# VRef_MEZ.net
KiCad netlist of a schematic drawn in Altium Designer
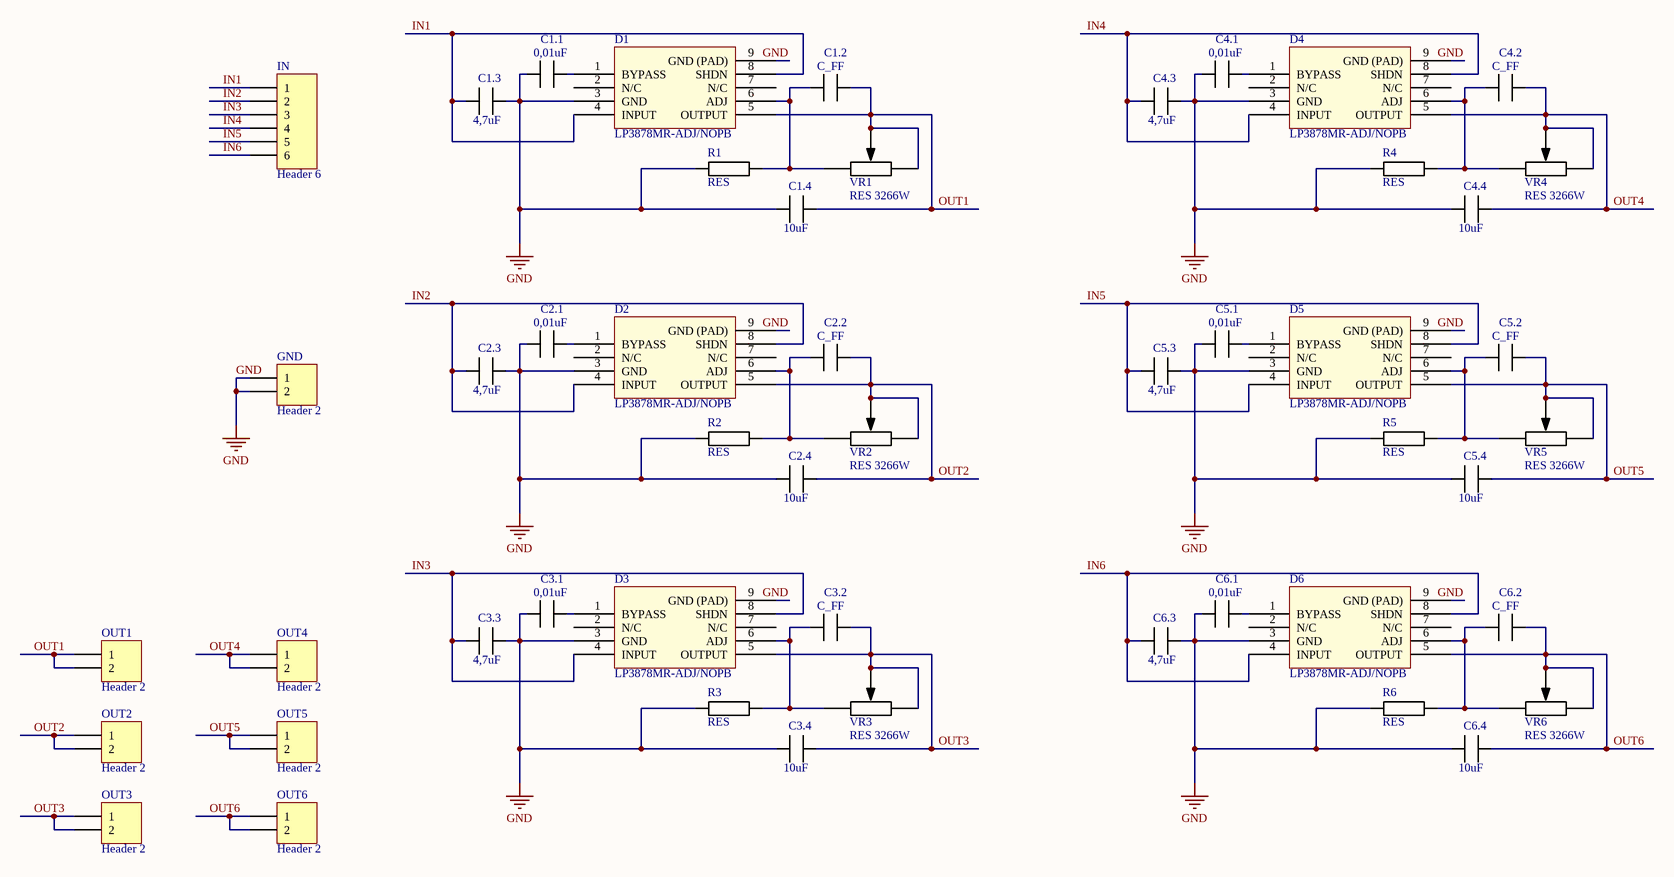
[diagram p0: VRef_MEZ.SchDoc]

(export (version "E")
  (design (tool "Eeschema 10.0.6"))
  (components
    (comp (ref "C1.1")
      (value "0,01uF")
      (footprint "aab_Passive:CAP_1812")
      (libsource (lib "aab_Schlib") (part "CAP"))
    )
    (comp (ref "C1.2")
      (value "C_FF")
      (footprint "aab_Passive:CAP_1812")
      (libsource (lib "aab_Schlib") (part "CAP"))
    )
    (comp (ref "C1.3")
      (value "4,7uF")
      (footprint "aab_Passive:CAP_1812")
      (libsource (lib "aab_Schlib") (part "CAP"))
    )
    (comp (ref "C1.4")
      (value "10uF")
      (footprint "aab_Passive:CAP_1812")
      (libsource (lib "aab_Schlib") (part "CAP"))
    )
    (comp (ref "C2.1")
      (value "0,01uF")
      (footprint "aab_Passive:CAP_1812")
      (libsource (lib "aab_Schlib") (part "CAP"))
    )
    (comp (ref "C2.2")
      (value "C_FF")
      (footprint "aab_Passive:CAP_1812")
      (libsource (lib "aab_Schlib") (part "CAP"))
    )
    (comp (ref "C2.3")
      (value "4,7uF")
      (footprint "aab_Passive:CAP_1812")
      (libsource (lib "aab_Schlib") (part "CAP"))
    )
    (comp (ref "C2.4")
      (value "10uF")
      (footprint "aab_Passive:CAP_1812")
      (libsource (lib "aab_Schlib") (part "CAP"))
    )
    (comp (ref "C3.1")
      (value "0,01uF")
      (footprint "aab_Passive:CAP_1812")
      (libsource (lib "aab_Schlib") (part "CAP"))
    )
    (comp (ref "C3.2")
      (value "C_FF")
      (footprint "aab_Passive:CAP_1812")
      (libsource (lib "aab_Schlib") (part "CAP"))
    )
    (comp (ref "C3.3")
      (value "4,7uF")
      (footprint "aab_Passive:CAP_1812")
      (libsource (lib "aab_Schlib") (part "CAP"))
    )
    (comp (ref "C3.4")
      (value "10uF")
      (footprint "aab_Passive:CAP_1812")
      (libsource (lib "aab_Schlib") (part "CAP"))
    )
    (comp (ref "C4.1")
      (value "0,01uF")
      (footprint "aab_Passive:CAP_1812")
      (libsource (lib "aab_Schlib") (part "CAP"))
    )
    (comp (ref "C4.2")
      (value "C_FF")
      (footprint "aab_Passive:CAP_1812")
      (libsource (lib "aab_Schlib") (part "CAP"))
    )
    (comp (ref "C4.3")
      (value "4,7uF")
      (footprint "aab_Passive:CAP_1812")
      (libsource (lib "aab_Schlib") (part "CAP"))
    )
    (comp (ref "C4.4")
      (value "10uF")
      (footprint "aab_Passive:CAP_1812")
      (libsource (lib "aab_Schlib") (part "CAP"))
    )
    (comp (ref "C5.1")
      (value "0,01uF")
      (footprint "aab_Passive:CAP_1812")
      (libsource (lib "aab_Schlib") (part "CAP"))
    )
    (comp (ref "C5.2")
      (value "C_FF")
      (footprint "aab_Passive:CAP_1812")
      (libsource (lib "aab_Schlib") (part "CAP"))
    )
    (comp (ref "C5.3")
      (value "4,7uF")
      (footprint "aab_Passive:CAP_1812")
      (libsource (lib "aab_Schlib") (part "CAP"))
    )
    (comp (ref "C5.4")
      (value "10uF")
      (footprint "aab_Passive:CAP_1812")
      (libsource (lib "aab_Schlib") (part "CAP"))
    )
    (comp (ref "C6.1")
      (value "0,01uF")
      (footprint "aab_Passive:CAP_1812")
      (libsource (lib "aab_Schlib") (part "CAP"))
    )
    (comp (ref "C6.2")
      (value "C_FF")
      (footprint "aab_Passive:CAP_1812")
      (libsource (lib "aab_Schlib") (part "CAP"))
    )
    (comp (ref "C6.3")
      (value "4,7uF")
      (footprint "aab_Passive:CAP_1812")
      (libsource (lib "aab_Schlib") (part "CAP"))
    )
    (comp (ref "C6.4")
      (value "10uF")
      (footprint "aab_Passive:CAP_1812")
      (libsource (lib "aab_Schlib") (part "CAP"))
    )
    (comp (ref "D1")
      (value "LP3878MR-ADJ/NOPB")
      (footprint "aab_Active:LP3878MR-ADJ/NOPB")
      (libsource (lib "aab_Schlib") (part "LP3878MR-ADJ/NOPB"))
    )
    (comp (ref "D2")
      (value "LP3878MR-ADJ/NOPB")
      (footprint "aab_Active:LP3878MR-ADJ/NOPB")
      (libsource (lib "aab_Schlib") (part "LP3878MR-ADJ/NOPB"))
    )
    (comp (ref "D3")
      (value "LP3878MR-ADJ/NOPB")
      (footprint "aab_Active:LP3878MR-ADJ/NOPB")
      (libsource (lib "aab_Schlib") (part "LP3878MR-ADJ/NOPB"))
    )
    (comp (ref "D4")
      (value "LP3878MR-ADJ/NOPB")
      (footprint "aab_Active:LP3878MR-ADJ/NOPB")
      (libsource (lib "aab_Schlib") (part "LP3878MR-ADJ/NOPB"))
    )
    (comp (ref "D5")
      (value "LP3878MR-ADJ/NOPB")
      (footprint "aab_Active:LP3878MR-ADJ/NOPB")
      (libsource (lib "aab_Schlib") (part "LP3878MR-ADJ/NOPB"))
    )
    (comp (ref "D6")
      (value "LP3878MR-ADJ/NOPB")
      (footprint "aab_Active:LP3878MR-ADJ/NOPB")
      (libsource (lib "aab_Schlib") (part "LP3878MR-ADJ/NOPB"))
    )
    (comp (ref "GND")
      (value "Header 2")
      (footprint "HDR1X2")
      (description "Header, 2-Pin")
      (fields (field (name "PUBLISHER") "Altium Limited"))
      (libsource (lib "Miscellaneous Connectors") (part "Header 2"))
    )
    (comp (ref "IN")
      (value "Header 6")
      (footprint "HDR1X6")
      (description "Header, 6-Pin")
      (fields (field (name "PUBLISHER") "Altium Limited"))
      (libsource (lib "Miscellaneous Connectors") (part "Header 6"))
    )
    (comp (ref "OUT1")
      (value "Header 2")
      (footprint "HDR1X2")
      (description "Header, 2-Pin")
      (fields (field (name "PUBLISHER") "Altium Limited"))
      (libsource (lib "Miscellaneous Connectors") (part "Header 2"))
    )
    (comp (ref "OUT2")
      (value "Header 2")
      (footprint "HDR1X2")
      (description "Header, 2-Pin")
      (fields (field (name "PUBLISHER") "Altium Limited"))
      (libsource (lib "Miscellaneous Connectors") (part "Header 2"))
    )
    (comp (ref "OUT3")
      (value "Header 2")
      (footprint "HDR1X2")
      (description "Header, 2-Pin")
      (fields (field (name "PUBLISHER") "Altium Limited"))
      (libsource (lib "Miscellaneous Connectors") (part "Header 2"))
    )
    (comp (ref "OUT4")
      (value "Header 2")
      (footprint "HDR1X2")
      (description "Header, 2-Pin")
      (fields (field (name "PUBLISHER") "Altium Limited"))
      (libsource (lib "Miscellaneous Connectors") (part "Header 2"))
    )
    (comp (ref "OUT5")
      (value "Header 2")
      (footprint "HDR1X2")
      (description "Header, 2-Pin")
      (fields (field (name "PUBLISHER") "Altium Limited"))
      (libsource (lib "Miscellaneous Connectors") (part "Header 2"))
    )
    (comp (ref "OUT6")
      (value "Header 2")
      (footprint "HDR1X2")
      (description "Header, 2-Pin")
      (fields (field (name "PUBLISHER") "Altium Limited"))
      (libsource (lib "Miscellaneous Connectors") (part "Header 2"))
    )
    (comp (ref "R1")
      (value "RES")
      (footprint "aab_Passive:RES_0805")
      (libsource (lib "aab_Schlib") (part "RES"))
    )
    (comp (ref "R2")
      (value "RES")
      (footprint "aab_Passive:RES_0805")
      (libsource (lib "aab_Schlib") (part "RES"))
    )
    (comp (ref "R3")
      (value "RES")
      (footprint "aab_Passive:RES_0805")
      (libsource (lib "aab_Schlib") (part "RES"))
    )
    (comp (ref "R4")
      (value "RES")
      (footprint "aab_Passive:RES_0805")
      (libsource (lib "aab_Schlib") (part "RES"))
    )
    (comp (ref "R5")
      (value "RES")
      (footprint "aab_Passive:RES_0805")
      (libsource (lib "aab_Schlib") (part "RES"))
    )
    (comp (ref "R6")
      (value "RES")
      (footprint "aab_Passive:RES_0805")
      (libsource (lib "aab_Schlib") (part "RES"))
    )
    (comp (ref "VR1")
      (value "RES 3266W")
      (footprint "aab_Passive:RES 3266W")
      (libsource (lib "aab_Schlib") (part "RES 3266W"))
    )
    (comp (ref "VR2")
      (value "RES 3266W")
      (footprint "aab_Passive:RES 3266W")
      (libsource (lib "aab_Schlib") (part "RES 3266W"))
    )
    (comp (ref "VR3")
      (value "RES 3266W")
      (footprint "aab_Passive:RES 3266W")
      (libsource (lib "aab_Schlib") (part "RES 3266W"))
    )
    (comp (ref "VR4")
      (value "RES 3266W")
      (footprint "aab_Passive:RES 3266W")
      (libsource (lib "aab_Schlib") (part "RES 3266W"))
    )
    (comp (ref "VR5")
      (value "RES 3266W")
      (footprint "aab_Passive:RES 3266W")
      (libsource (lib "aab_Schlib") (part "RES 3266W"))
    )
    (comp (ref "VR6")
      (value "RES 3266W")
      (footprint "aab_Passive:RES 3266W")
      (libsource (lib "aab_Schlib") (part "RES 3266W"))
    )
  )
  (nets
    (net (code "1") (name "/IN1") (class "Default")
      (node (ref "C1.3") (pin "2") (pinfunction "2_2") (pintype "passive"))
      (node (ref "D1") (pin "4") (pinfunction "INPUT_4") (pintype "passive"))
      (node (ref "D1") (pin "8") (pinfunction "SHDN_8") (pintype "passive"))
      (node (ref "IN") (pin "1") (pinfunction "1_1") (pintype "passive"))
    )
    (net (code "2") (name "/IN2") (class "Default")
      (node (ref "C2.3") (pin "2") (pinfunction "2_2") (pintype "passive"))
      (node (ref "D2") (pin "4") (pinfunction "INPUT_4") (pintype "passive"))
      (node (ref "D2") (pin "8") (pinfunction "SHDN_8") (pintype "passive"))
      (node (ref "IN") (pin "2") (pinfunction "2_2") (pintype "passive"))
    )
    (net (code "3") (name "/IN3") (class "Default")
      (node (ref "C3.3") (pin "2") (pinfunction "2_2") (pintype "passive"))
      (node (ref "D3") (pin "4") (pinfunction "INPUT_4") (pintype "passive"))
      (node (ref "D3") (pin "8") (pinfunction "SHDN_8") (pintype "passive"))
      (node (ref "IN") (pin "3") (pinfunction "3_3") (pintype "passive"))
    )
    (net (code "4") (name "/IN4") (class "Default")
      (node (ref "C4.3") (pin "2") (pinfunction "2_2") (pintype "passive"))
      (node (ref "D4") (pin "4") (pinfunction "INPUT_4") (pintype "passive"))
      (node (ref "D4") (pin "8") (pinfunction "SHDN_8") (pintype "passive"))
      (node (ref "IN") (pin "4") (pinfunction "4_4") (pintype "passive"))
    )
    (net (code "5") (name "/IN5") (class "Default")
      (node (ref "C5.3") (pin "2") (pinfunction "2_2") (pintype "passive"))
      (node (ref "D5") (pin "4") (pinfunction "INPUT_4") (pintype "passive"))
      (node (ref "D5") (pin "8") (pinfunction "SHDN_8") (pintype "passive"))
      (node (ref "IN") (pin "5") (pinfunction "5_5") (pintype "passive"))
    )
    (net (code "6") (name "/IN6") (class "Default")
      (node (ref "C6.3") (pin "2") (pinfunction "2_2") (pintype "passive"))
      (node (ref "D6") (pin "4") (pinfunction "INPUT_4") (pintype "passive"))
      (node (ref "D6") (pin "8") (pinfunction "SHDN_8") (pintype "passive"))
      (node (ref "IN") (pin "6") (pinfunction "6_6") (pintype "passive"))
    )
    (net (code "7") (name "/OUT1") (class "Default")
      (node (ref "C1.2") (pin "1") (pinfunction "1_1") (pintype "passive"))
      (node (ref "C1.4") (pin "1") (pinfunction "1_1") (pintype "passive"))
      (node (ref "D1") (pin "5") (pinfunction "OUTPUT_5") (pintype "passive"))
      (node (ref "OUT1") (pin "1") (pinfunction "1_1") (pintype "passive"))
      (node (ref "OUT1") (pin "2") (pinfunction "2_2") (pintype "passive"))
      (node (ref "VR1") (pin "2") (pinfunction "2_2") (pintype "passive"))
      (node (ref "VR1") (pin "3") (pinfunction "3_3") (pintype "passive"))
    )
    (net (code "8") (name "/OUT2") (class "Default")
      (node (ref "C2.2") (pin "1") (pinfunction "1_1") (pintype "passive"))
      (node (ref "C2.4") (pin "1") (pinfunction "1_1") (pintype "passive"))
      (node (ref "D2") (pin "5") (pinfunction "OUTPUT_5") (pintype "passive"))
      (node (ref "OUT2") (pin "1") (pinfunction "1_1") (pintype "passive"))
      (node (ref "OUT2") (pin "2") (pinfunction "2_2") (pintype "passive"))
      (node (ref "VR2") (pin "2") (pinfunction "2_2") (pintype "passive"))
      (node (ref "VR2") (pin "3") (pinfunction "3_3") (pintype "passive"))
    )
    (net (code "9") (name "/OUT3") (class "Default")
      (node (ref "C3.2") (pin "1") (pinfunction "1_1") (pintype "passive"))
      (node (ref "C3.4") (pin "1") (pinfunction "1_1") (pintype "passive"))
      (node (ref "D3") (pin "5") (pinfunction "OUTPUT_5") (pintype "passive"))
      (node (ref "OUT3") (pin "1") (pinfunction "1_1") (pintype "passive"))
      (node (ref "OUT3") (pin "2") (pinfunction "2_2") (pintype "passive"))
      (node (ref "VR3") (pin "2") (pinfunction "2_2") (pintype "passive"))
      (node (ref "VR3") (pin "3") (pinfunction "3_3") (pintype "passive"))
    )
    (net (code "10") (name "/OUT4") (class "Default")
      (node (ref "C4.2") (pin "1") (pinfunction "1_1") (pintype "passive"))
      (node (ref "C4.4") (pin "1") (pinfunction "1_1") (pintype "passive"))
      (node (ref "D4") (pin "5") (pinfunction "OUTPUT_5") (pintype "passive"))
      (node (ref "OUT4") (pin "1") (pinfunction "1_1") (pintype "passive"))
      (node (ref "OUT4") (pin "2") (pinfunction "2_2") (pintype "passive"))
      (node (ref "VR4") (pin "2") (pinfunction "2_2") (pintype "passive"))
      (node (ref "VR4") (pin "3") (pinfunction "3_3") (pintype "passive"))
    )
    (net (code "11") (name "/OUT5") (class "Default")
      (node (ref "C5.2") (pin "1") (pinfunction "1_1") (pintype "passive"))
      (node (ref "C5.4") (pin "1") (pinfunction "1_1") (pintype "passive"))
      (node (ref "D5") (pin "5") (pinfunction "OUTPUT_5") (pintype "passive"))
      (node (ref "OUT5") (pin "1") (pinfunction "1_1") (pintype "passive"))
      (node (ref "OUT5") (pin "2") (pinfunction "2_2") (pintype "passive"))
      (node (ref "VR5") (pin "2") (pinfunction "2_2") (pintype "passive"))
      (node (ref "VR5") (pin "3") (pinfunction "3_3") (pintype "passive"))
    )
    (net (code "12") (name "/OUT6") (class "Default")
      (node (ref "C6.2") (pin "1") (pinfunction "1_1") (pintype "passive"))
      (node (ref "C6.4") (pin "1") (pinfunction "1_1") (pintype "passive"))
      (node (ref "D6") (pin "5") (pinfunction "OUTPUT_5") (pintype "passive"))
      (node (ref "OUT6") (pin "1") (pinfunction "1_1") (pintype "passive"))
      (node (ref "OUT6") (pin "2") (pinfunction "2_2") (pintype "passive"))
      (node (ref "VR6") (pin "2") (pinfunction "2_2") (pintype "passive"))
      (node (ref "VR6") (pin "3") (pinfunction "3_3") (pintype "passive"))
    )
    (net (code "13") (name "GND") (class "Default")
      (node (ref "C1.1") (pin "2") (pinfunction "2_2") (pintype "passive"))
      (node (ref "C1.3") (pin "1") (pinfunction "1_1") (pintype "passive"))
      (node (ref "C1.4") (pin "2") (pinfunction "2_2") (pintype "passive"))
      (node (ref "C2.1") (pin "2") (pinfunction "2_2") (pintype "passive"))
      (node (ref "C2.3") (pin "1") (pinfunction "1_1") (pintype "passive"))
      (node (ref "C2.4") (pin "2") (pinfunction "2_2") (pintype "passive"))
      (node (ref "C3.1") (pin "2") (pinfunction "2_2") (pintype "passive"))
      (node (ref "C3.3") (pin "1") (pinfunction "1_1") (pintype "passive"))
      (node (ref "C3.4") (pin "2") (pinfunction "2_2") (pintype "passive"))
      (node (ref "C4.1") (pin "2") (pinfunction "2_2") (pintype "passive"))
      (node (ref "C4.3") (pin "1") (pinfunction "1_1") (pintype "passive"))
      (node (ref "C4.4") (pin "2") (pinfunction "2_2") (pintype "passive"))
      (node (ref "C5.1") (pin "2") (pinfunction "2_2") (pintype "passive"))
      (node (ref "C5.3") (pin "1") (pinfunction "1_1") (pintype "passive"))
      (node (ref "C5.4") (pin "2") (pinfunction "2_2") (pintype "passive"))
      (node (ref "C6.1") (pin "2") (pinfunction "2_2") (pintype "passive"))
      (node (ref "C6.3") (pin "1") (pinfunction "1_1") (pintype "passive"))
      (node (ref "C6.4") (pin "2") (pinfunction "2_2") (pintype "passive"))
      (node (ref "D1") (pin "3") (pinfunction "GND_3") (pintype "passive"))
      (node (ref "D1") (pin "9") (pinfunction "GND_(PAD)_9") (pintype "passive"))
      (node (ref "D2") (pin "3") (pinfunction "GND_3") (pintype "passive"))
      (node (ref "D2") (pin "9") (pinfunction "GND_(PAD)_9") (pintype "passive"))
      (node (ref "D3") (pin "3") (pinfunction "GND_3") (pintype "passive"))
      (node (ref "D3") (pin "9") (pinfunction "GND_(PAD)_9") (pintype "passive"))
      (node (ref "D4") (pin "3") (pinfunction "GND_3") (pintype "passive"))
      (node (ref "D4") (pin "9") (pinfunction "GND_(PAD)_9") (pintype "passive"))
      (node (ref "D5") (pin "3") (pinfunction "GND_3") (pintype "passive"))
      (node (ref "D5") (pin "9") (pinfunction "GND_(PAD)_9") (pintype "passive"))
      (node (ref "D6") (pin "3") (pinfunction "GND_3") (pintype "passive"))
      (node (ref "D6") (pin "9") (pinfunction "GND_(PAD)_9") (pintype "passive"))
      (node (ref "GND") (pin "1") (pinfunction "1_1") (pintype "passive"))
      (node (ref "GND") (pin "2") (pinfunction "2_2") (pintype "passive"))
      (node (ref "R1") (pin "1") (pinfunction "1_1") (pintype "passive"))
      (node (ref "R2") (pin "1") (pinfunction "1_1") (pintype "passive"))
      (node (ref "R3") (pin "1") (pinfunction "1_1") (pintype "passive"))
      (node (ref "R4") (pin "1") (pinfunction "1_1") (pintype "passive"))
      (node (ref "R5") (pin "1") (pinfunction "1_1") (pintype "passive"))
      (node (ref "R6") (pin "1") (pinfunction "1_1") (pintype "passive"))
    )
    (net (code "14") (name "Net-(D1-ADJ)") (class "Default")
      (node (ref "C1.2") (pin "2") (pinfunction "2_2") (pintype "passive"))
      (node (ref "D1") (pin "6") (pinfunction "ADJ_6") (pintype "passive"))
      (node (ref "R1") (pin "2") (pinfunction "2_2") (pintype "passive"))
      (node (ref "VR1") (pin "1") (pinfunction "1_1") (pintype "passive"))
    )
    (net (code "15") (name "Net-(D1-BYPASS)") (class "Default")
      (node (ref "C1.1") (pin "1") (pinfunction "1_1") (pintype "passive"))
      (node (ref "D1") (pin "1") (pinfunction "BYPASS_1") (pintype "passive"))
    )
    (net (code "16") (name "Net-(D2-ADJ)") (class "Default")
      (node (ref "C2.2") (pin "2") (pinfunction "2_2") (pintype "passive"))
      (node (ref "D2") (pin "6") (pinfunction "ADJ_6") (pintype "passive"))
      (node (ref "R2") (pin "2") (pinfunction "2_2") (pintype "passive"))
      (node (ref "VR2") (pin "1") (pinfunction "1_1") (pintype "passive"))
    )
    (net (code "17") (name "Net-(D2-BYPASS)") (class "Default")
      (node (ref "C2.1") (pin "1") (pinfunction "1_1") (pintype "passive"))
      (node (ref "D2") (pin "1") (pinfunction "BYPASS_1") (pintype "passive"))
    )
    (net (code "18") (name "Net-(D3-ADJ)") (class "Default")
      (node (ref "C3.2") (pin "2") (pinfunction "2_2") (pintype "passive"))
      (node (ref "D3") (pin "6") (pinfunction "ADJ_6") (pintype "passive"))
      (node (ref "R3") (pin "2") (pinfunction "2_2") (pintype "passive"))
      (node (ref "VR3") (pin "1") (pinfunction "1_1") (pintype "passive"))
    )
    (net (code "19") (name "Net-(D3-BYPASS)") (class "Default")
      (node (ref "C3.1") (pin "1") (pinfunction "1_1") (pintype "passive"))
      (node (ref "D3") (pin "1") (pinfunction "BYPASS_1") (pintype "passive"))
    )
    (net (code "20") (name "Net-(D4-ADJ)") (class "Default")
      (node (ref "C4.2") (pin "2") (pinfunction "2_2") (pintype "passive"))
      (node (ref "D4") (pin "6") (pinfunction "ADJ_6") (pintype "passive"))
      (node (ref "R4") (pin "2") (pinfunction "2_2") (pintype "passive"))
      (node (ref "VR4") (pin "1") (pinfunction "1_1") (pintype "passive"))
    )
    (net (code "21") (name "Net-(D4-BYPASS)") (class "Default")
      (node (ref "C4.1") (pin "1") (pinfunction "1_1") (pintype "passive"))
      (node (ref "D4") (pin "1") (pinfunction "BYPASS_1") (pintype "passive"))
    )
    (net (code "22") (name "Net-(D5-ADJ)") (class "Default")
      (node (ref "C5.2") (pin "2") (pinfunction "2_2") (pintype "passive"))
      (node (ref "D5") (pin "6") (pinfunction "ADJ_6") (pintype "passive"))
      (node (ref "R5") (pin "2") (pinfunction "2_2") (pintype "passive"))
      (node (ref "VR5") (pin "1") (pinfunction "1_1") (pintype "passive"))
    )
    (net (code "23") (name "Net-(D5-BYPASS)") (class "Default")
      (node (ref "C5.1") (pin "1") (pinfunction "1_1") (pintype "passive"))
      (node (ref "D5") (pin "1") (pinfunction "BYPASS_1") (pintype "passive"))
    )
    (net (code "24") (name "Net-(D6-ADJ)") (class "Default")
      (node (ref "C6.2") (pin "2") (pinfunction "2_2") (pintype "passive"))
      (node (ref "D6") (pin "6") (pinfunction "ADJ_6") (pintype "passive"))
      (node (ref "R6") (pin "2") (pinfunction "2_2") (pintype "passive"))
      (node (ref "VR6") (pin "1") (pinfunction "1_1") (pintype "passive"))
    )
    (net (code "25") (name "Net-(D6-BYPASS)") (class "Default")
      (node (ref "C6.1") (pin "1") (pinfunction "1_1") (pintype "passive"))
      (node (ref "D6") (pin "1") (pinfunction "BYPASS_1") (pintype "passive"))
    )
    (net (code "26") (name "unconnected-(D1-N{slash}C-Pad2)") (class "Default")
      (node (ref "D1") (pin "2") (pinfunction "N/C_2") (pintype "passive"))
    )
    (net (code "27") (name "unconnected-(D1-N{slash}C-Pad7)") (class "Default")
      (node (ref "D1") (pin "7") (pinfunction "N/C_7") (pintype "passive"))
    )
    (net (code "28") (name "unconnected-(D2-N{slash}C-Pad2)") (class "Default")
      (node (ref "D2") (pin "2") (pinfunction "N/C_2") (pintype "passive"))
    )
    (net (code "29") (name "unconnected-(D2-N{slash}C-Pad7)") (class "Default")
      (node (ref "D2") (pin "7") (pinfunction "N/C_7") (pintype "passive"))
    )
    (net (code "30") (name "unconnected-(D3-N{slash}C-Pad2)") (class "Default")
      (node (ref "D3") (pin "2") (pinfunction "N/C_2") (pintype "passive"))
    )
    (net (code "31") (name "unconnected-(D3-N{slash}C-Pad7)") (class "Default")
      (node (ref "D3") (pin "7") (pinfunction "N/C_7") (pintype "passive"))
    )
    (net (code "32") (name "unconnected-(D4-N{slash}C-Pad2)") (class "Default")
      (node (ref "D4") (pin "2") (pinfunction "N/C_2") (pintype "passive"))
    )
    (net (code "33") (name "unconnected-(D4-N{slash}C-Pad7)") (class "Default")
      (node (ref "D4") (pin "7") (pinfunction "N/C_7") (pintype "passive"))
    )
    (net (code "34") (name "unconnected-(D5-N{slash}C-Pad2)") (class "Default")
      (node (ref "D5") (pin "2") (pinfunction "N/C_2") (pintype "passive"))
    )
    (net (code "35") (name "unconnected-(D5-N{slash}C-Pad7)") (class "Default")
      (node (ref "D5") (pin "7") (pinfunction "N/C_7") (pintype "passive"))
    )
    (net (code "36") (name "unconnected-(D6-N{slash}C-Pad2)") (class "Default")
      (node (ref "D6") (pin "2") (pinfunction "N/C_2") (pintype "passive"))
    )
    (net (code "37") (name "unconnected-(D6-N{slash}C-Pad7)") (class "Default")
      (node (ref "D6") (pin "7") (pinfunction "N/C_7") (pintype "passive"))
    )
  )
)
